# Mozard_2020-10-18.net
KiCad netlist of a schematic drawn in EAGLE
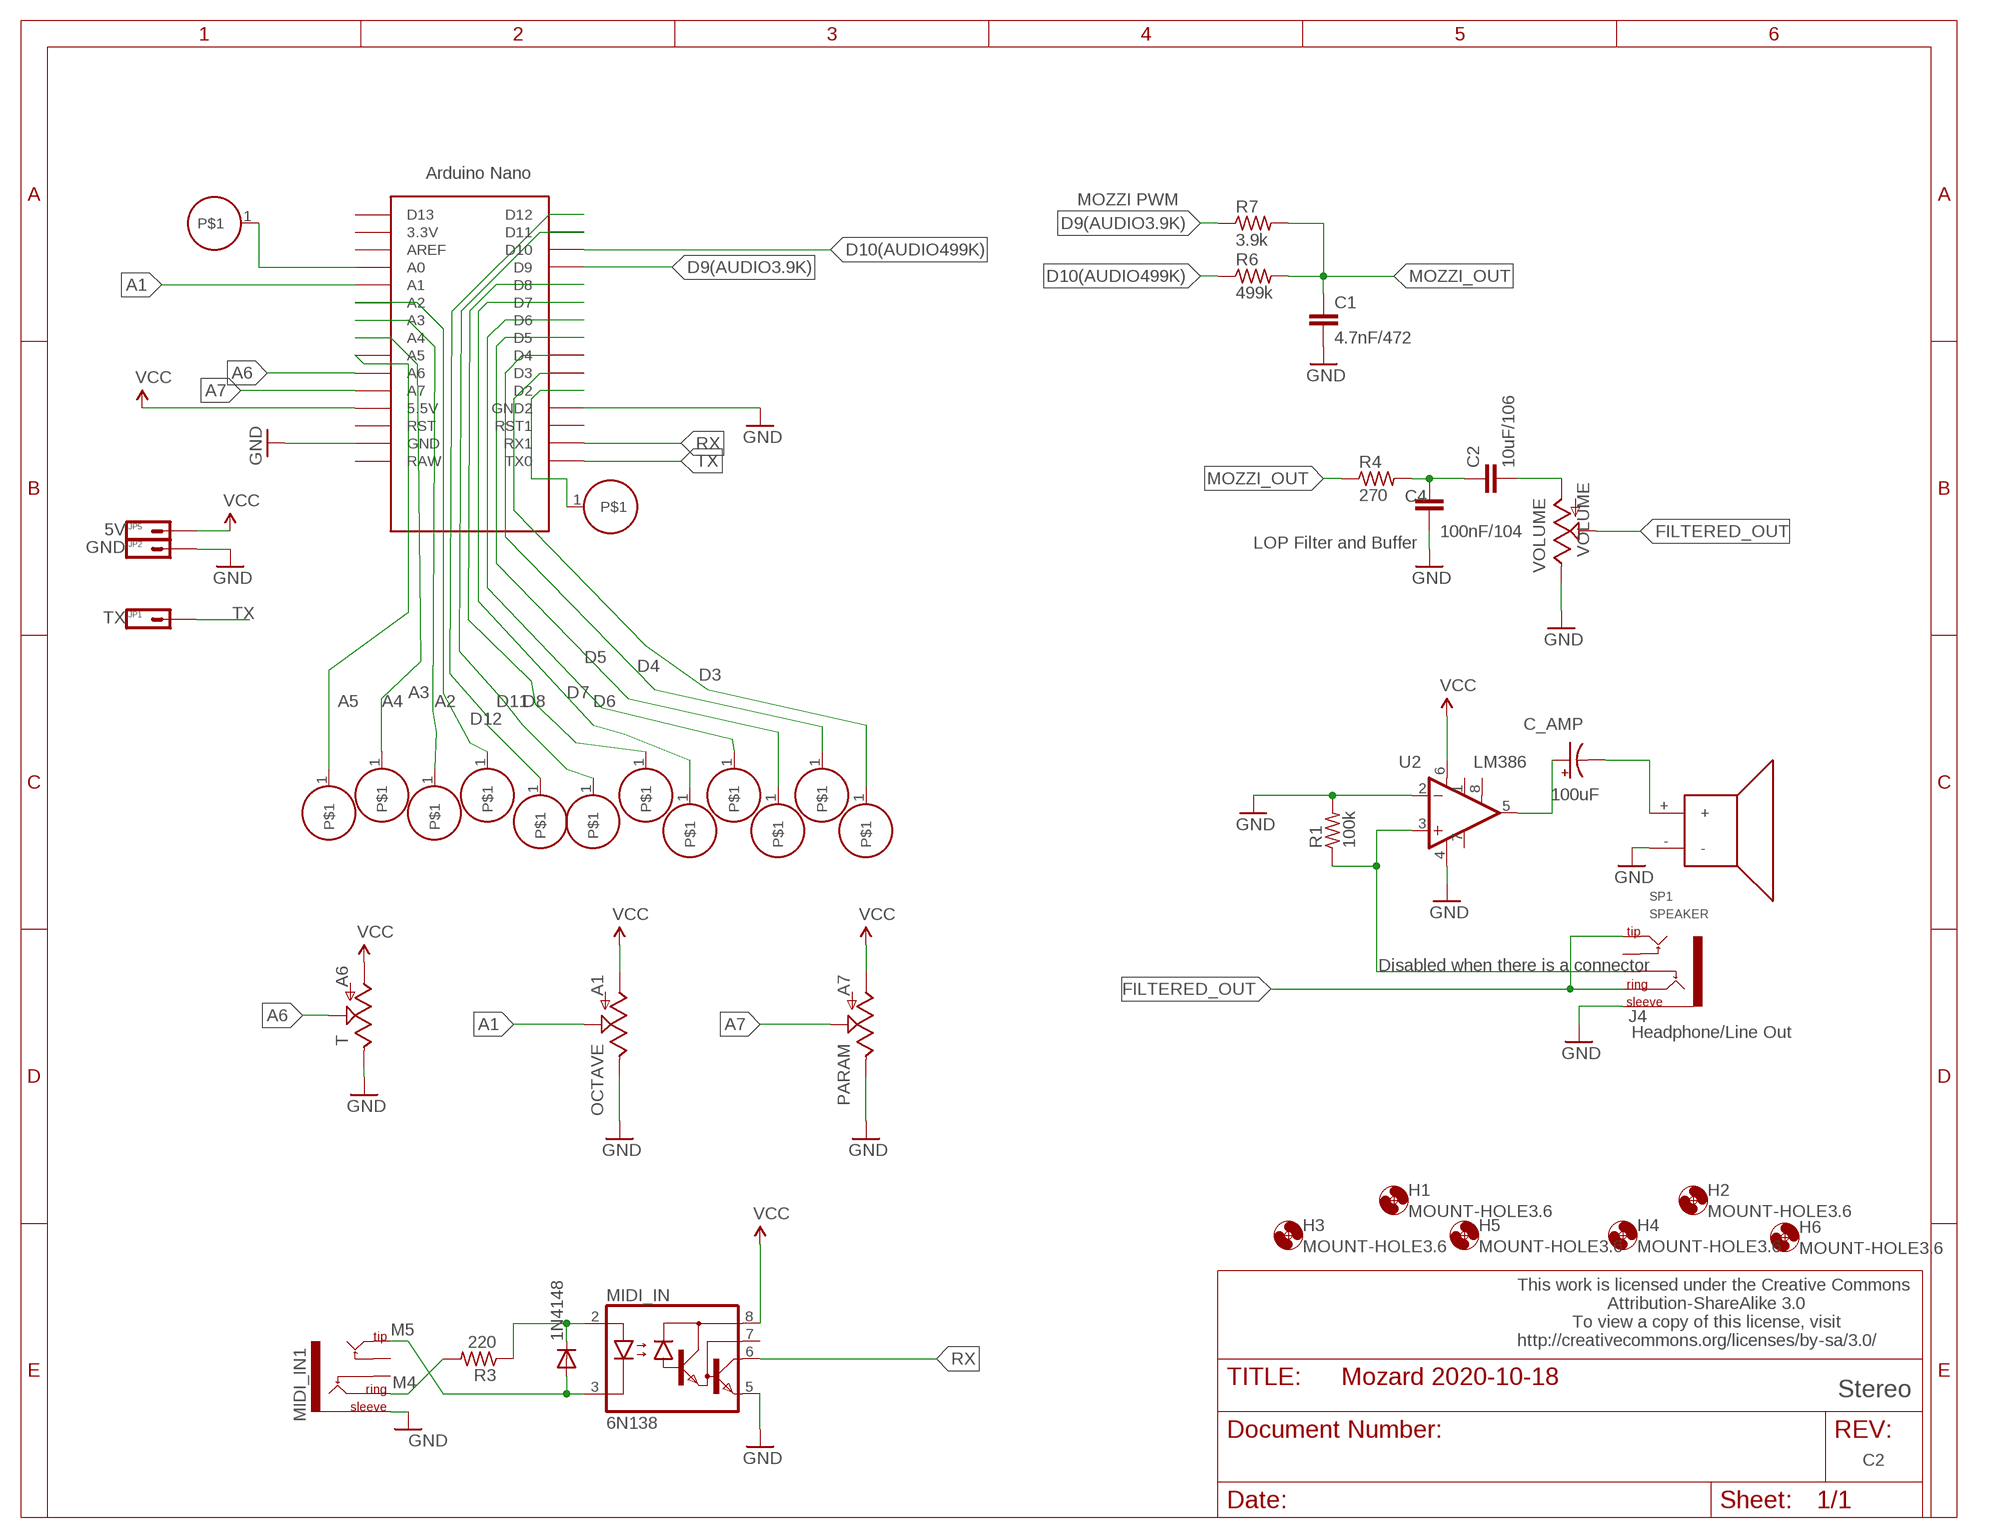
[diagram p0: schematic, sheet 1]

(export (version "E")
  (design (tool "Eeschema 10.0.6"))
  (components
    (comp (ref "1N4148")
      (value "1N4148")
      (footprint "eagle-import:DO41-10")
      (libsource (lib "eagle-import") (part "DIODE"))
    )
    (comp (ref "C1")
      (value "4.7nF/472")
      (footprint "eagle-import:CAP-PTH-SMALL-KIT")
      (libsource (lib "eagle-import") (part "0.1UF-50V-20%(PTH)KIT-EZ"))
    )
    (comp (ref "C2")
      (value "10uF/106")
      (footprint "eagle-import:CAP-PTH-SMALL-KIT")
      (libsource (lib "eagle-import") (part "0.1UF-50V-20%(PTH)KIT-EZ"))
    )
    (comp (ref "C4")
      (value "100nF/104")
      (footprint "eagle-import:CAP-PTH-SMALL-KIT")
      (libsource (lib "eagle-import") (part "0.1UF-50V-20%(PTH)KIT-EZ"))
    )
    (comp (ref "C_AMP")
      (value "100uF")
      (footprint "eagle-import:CPOL-RADIAL-10UF-25V")
      (libsource (lib "eagle-import") (part "CPOL-RADIAL-10UF-25V"))
    )
    (comp (ref "H1")
      (value "MOUNT-HOLE3.6")
      (footprint "eagle-import:3,6")
      (libsource (lib "eagle-import") (part "MOUNT-HOLE3.6"))
    )
    (comp (ref "H2")
      (value "MOUNT-HOLE3.6")
      (footprint "eagle-import:3,6")
      (libsource (lib "eagle-import") (part "MOUNT-HOLE3.6"))
    )
    (comp (ref "H3")
      (value "MOUNT-HOLE3.6")
      (footprint "eagle-import:3,6")
      (libsource (lib "eagle-import") (part "MOUNT-HOLE3.6"))
    )
    (comp (ref "H4")
      (value "MOUNT-HOLE3.6")
      (footprint "eagle-import:3,6")
      (libsource (lib "eagle-import") (part "MOUNT-HOLE3.6"))
    )
    (comp (ref "H5")
      (value "MOUNT-HOLE3.6")
      (footprint "eagle-import:3,6")
      (libsource (lib "eagle-import") (part "MOUNT-HOLE3.6"))
    )
    (comp (ref "H6")
      (value "MOUNT-HOLE3.6")
      (footprint "eagle-import:3,6")
      (libsource (lib "eagle-import") (part "MOUNT-HOLE3.6"))
    )
    (comp (ref "J4")
      (value "Headphone/Line Out")
      (footprint "eagle-import:AUDIO-JACK")
      (libsource (lib "eagle-import") (part "AUDIO-JACKPTH"))
    )
    (comp (ref "JP1")
      (value "TX")
      (footprint "eagle-import:1X01_SIDE_NAME")
      (libsource (lib "eagle-import") (part "HEADER-1X1"))
    )
    (comp (ref "JP2")
      (value "GND")
      (footprint "eagle-import:1X01_SIDE_NAME")
      (libsource (lib "eagle-import") (part "HEADER-1X1"))
    )
    (comp (ref "JP5")
      (value "5V")
      (footprint "eagle-import:1X01_SIDE_NAME")
      (libsource (lib "eagle-import") (part "HEADER-1X1"))
    )
    (comp (ref "MIDI_IN")
      (value "6N138")
      (footprint "eagle-import:DIL08")
      (fields (field (name "MF") "VISHAY/TELEFUNKEN"))
      (libsource (lib "eagle-import") (part "6N138"))
    )
    (comp (ref "MIDI_IN1")
      (value "AUDIO-JACKKIT")
      (footprint "eagle-import:AUDIO-JACK-KIT")
      (libsource (lib "eagle-import") (part "AUDIO-JACKKIT"))
    )
    (comp (ref "OCTAVE")
      (value "A1")
      (footprint "eagle-import:ALPS_POT")
      (libsource (lib "eagle-import") (part "POT"))
    )
    (comp (ref "PARAM")
      (value "A7")
      (footprint "eagle-import:ALPS_POT")
      (libsource (lib "eagle-import") (part "POT"))
    )
    (comp (ref "R1")
      (value "100k")
      (footprint "eagle-import:0204_7")
      (libsource (lib "eagle-import") (part "R-US_0204/7"))
    )
    (comp (ref "R3")
      (value "220")
      (footprint "eagle-import:0204_5")
      (libsource (lib "eagle-import") (part "R-US_0204/5"))
    )
    (comp (ref "R4")
      (value "270")
      (footprint "eagle-import:0204_7")
      (libsource (lib "eagle-import") (part "R-US_0204/7"))
    )
    (comp (ref "R6")
      (value "499k")
      (footprint "eagle-import:0204_7")
      (libsource (lib "eagle-import") (part "R-US_0204/7"))
    )
    (comp (ref "R7")
      (value "3.9k")
      (footprint "eagle-import:0204_7")
      (libsource (lib "eagle-import") (part "R-US_0204/7"))
    )
    (comp (ref "SP1")
      (value "SPEAKER")
      (footprint "eagle-import:PCB_MOUNT_SPEAKER")
      (fields (field (name "MFG") "SANCO"))
      (libsource (lib "eagle-import") (part "SPEAKERPCB_MOUNT"))
    )
    (comp (ref "T")
      (value "A6")
      (footprint "eagle-import:ALPS_POT")
      (libsource (lib "eagle-import") (part "POT"))
    )
    (comp (ref "U$1")
      (value "NANO")
      (footprint "eagle-import:NANO")
      (libsource (lib "eagle-import") (part "NANO"))
    )
    (comp (ref "U$2")
      (value "PCB-TOUCHPAD-1-PIN")
      (footprint "eagle-import:PCB-TOUCHPAD-1-PIN")
      (libsource (lib "eagle-import") (part "PCB-TOUCHPAD-1-PIN"))
    )
    (comp (ref "U$3")
      (value "PCB-TOUCHPAD-1-PIN")
      (footprint "eagle-import:PCB-TOUCHPAD-1-PIN")
      (libsource (lib "eagle-import") (part "PCB-TOUCHPAD-1-PIN"))
    )
    (comp (ref "U$4")
      (value "PCB-TOUCHPAD-1-PIN")
      (footprint "eagle-import:PCB-TOUCHPAD-1-PIN")
      (libsource (lib "eagle-import") (part "PCB-TOUCHPAD-1-PIN"))
    )
    (comp (ref "U$5")
      (value "PCB-TOUCHPAD-1-PIN")
      (footprint "eagle-import:PCB-TOUCHPAD-1-PIN")
      (libsource (lib "eagle-import") (part "PCB-TOUCHPAD-1-PIN"))
    )
    (comp (ref "U$6")
      (value "PCB-TOUCHPAD-1-PIN")
      (footprint "eagle-import:PCB-TOUCHPAD-1-PIN")
      (libsource (lib "eagle-import") (part "PCB-TOUCHPAD-1-PIN"))
    )
    (comp (ref "U$7")
      (value "PCB-TOUCHPAD-1-PIN")
      (footprint "eagle-import:PCB-TOUCHPAD-1-PIN")
      (libsource (lib "eagle-import") (part "PCB-TOUCHPAD-1-PIN"))
    )
    (comp (ref "U$8")
      (value "PCB-TOUCHPAD-1-PIN")
      (footprint "eagle-import:PCB-TOUCHPAD-1-PIN")
      (libsource (lib "eagle-import") (part "PCB-TOUCHPAD-1-PIN"))
    )
    (comp (ref "U$9")
      (value "PCB-TOUCHPAD-1-PIN")
      (footprint "eagle-import:PCB-TOUCHPAD-1-PIN")
      (libsource (lib "eagle-import") (part "PCB-TOUCHPAD-1-PIN"))
    )
    (comp (ref "U$10")
      (value "PCB-TOUCHPAD-1-PIN")
      (footprint "eagle-import:PCB-TOUCHPAD-1-PIN")
      (libsource (lib "eagle-import") (part "PCB-TOUCHPAD-1-PIN"))
    )
    (comp (ref "U$11")
      (value "PCB-TOUCHPAD-1-PIN")
      (footprint "eagle-import:PCB-TOUCHPAD-1-PIN")
      (libsource (lib "eagle-import") (part "PCB-TOUCHPAD-1-PIN"))
    )
    (comp (ref "U$12")
      (value "PCB-TOUCHPAD-1-PIN")
      (footprint "eagle-import:PCB-TOUCHPAD-1-PIN")
      (libsource (lib "eagle-import") (part "PCB-TOUCHPAD-1-PIN"))
    )
    (comp (ref "U$13")
      (value "PCB-TOUCHPAD-1-PIN")
      (footprint "eagle-import:PCB-TOUCHPAD-1-PIN")
      (libsource (lib "eagle-import") (part "PCB-TOUCHPAD-1-PIN"))
    )
    (comp (ref "U$14")
      (value "PCB-TOUCHPAD-1-PIN")
      (footprint "eagle-import:PCB-TOUCHPAD-1-PIN")
      (libsource (lib "eagle-import") (part "PCB-TOUCHPAD-1-PIN"))
    )
    (comp (ref "U$15")
      (value "PCB-TOUCHPAD-1-PIN")
      (footprint "eagle-import:PCB-TOUCHPAD-1-PIN")
      (libsource (lib "eagle-import") (part "PCB-TOUCHPAD-1-PIN"))
    )
    (comp (ref "U2")
      (value "LM386")
      (footprint "eagle-import:DIP08")
      (libsource (lib "eagle-import") (part "LM386"))
    )
    (comp (ref "VOLUME")
      (value "VOLUME")
      (footprint "eagle-import:ALPS_POT")
      (libsource (lib "eagle-import") (part "POT"))
    )
  )
  (nets
    (net (code "1") (name "/A2") (class "Default")
      (node (ref "U$1") (pin "A2") (pinfunction "A2_A2") (pintype "bidirectional"))
      (node (ref "U$5") (pin "1") (pinfunction "P$1_1") (pintype "bidirectional"))
    )
    (net (code "2") (name "/A3") (class "Default")
      (node (ref "U$1") (pin "A3") (pinfunction "A3_A3") (pintype "bidirectional"))
      (node (ref "U$4") (pin "1") (pinfunction "P$1_1") (pintype "bidirectional"))
    )
    (net (code "3") (name "/A4") (class "Default")
      (node (ref "U$1") (pin "A4") (pinfunction "A4_A4") (pintype "bidirectional"))
      (node (ref "U$3") (pin "1") (pinfunction "P$1_1") (pintype "bidirectional"))
    )
    (net (code "4") (name "/A5") (class "Default")
      (node (ref "U$1") (pin "A5") (pinfunction "A5_A5") (pintype "bidirectional"))
      (node (ref "U$2") (pin "1") (pinfunction "P$1_1") (pintype "bidirectional"))
    )
    (net (code "5") (name "/D3") (class "Default")
      (node (ref "U$1") (pin "D3") (pinfunction "D3_D3") (pintype "bidirectional"))
      (node (ref "U$13") (pin "1") (pinfunction "P$1_1") (pintype "bidirectional"))
    )
    (net (code "6") (name "/D4") (class "Default")
      (node (ref "U$1") (pin "D4") (pinfunction "D4_D4") (pintype "bidirectional"))
      (node (ref "U$12") (pin "1") (pinfunction "P$1_1") (pintype "bidirectional"))
    )
    (net (code "7") (name "/D5") (class "Default")
      (node (ref "U$1") (pin "D5") (pinfunction "D5_D5") (pintype "bidirectional"))
      (node (ref "U$11") (pin "1") (pinfunction "P$1_1") (pintype "bidirectional"))
    )
    (net (code "8") (name "/D6") (class "Default")
      (node (ref "U$1") (pin "D6") (pinfunction "D6_D6") (pintype "bidirectional"))
      (node (ref "U$10") (pin "1") (pinfunction "P$1_1") (pintype "bidirectional"))
    )
    (net (code "9") (name "/D7") (class "Default")
      (node (ref "U$1") (pin "D7") (pinfunction "D7_D7") (pintype "bidirectional"))
      (node (ref "U$9") (pin "1") (pinfunction "P$1_1") (pintype "bidirectional"))
    )
    (net (code "10") (name "/D8") (class "Default")
      (node (ref "U$1") (pin "D8") (pinfunction "D8_D8") (pintype "bidirectional"))
      (node (ref "U$8") (pin "1") (pinfunction "P$1_1") (pintype "bidirectional"))
    )
    (net (code "11") (name "/D11") (class "Default")
      (node (ref "U$1") (pin "D11") (pinfunction "D11_D11") (pintype "bidirectional"))
      (node (ref "U$7") (pin "1") (pinfunction "P$1_1") (pintype "bidirectional"))
    )
    (net (code "12") (name "/D12") (class "Default")
      (node (ref "U$1") (pin "D12") (pinfunction "D12_D12") (pintype "bidirectional"))
      (node (ref "U$6") (pin "1") (pinfunction "P$1_1") (pintype "bidirectional"))
    )
    (net (code "13") (name "/M4") (class "Default")
      (node (ref "MIDI_IN1") (pin "RING") (pinfunction "RING_RING") (pintype "bidirectional"))
      (node (ref "R3") (pin "2") (pinfunction "2_2") (pintype "passive"))
    )
    (net (code "14") (name "/M5") (class "Default")
      (node (ref "1N4148") (pin "A") (pinfunction "A_A") (pintype "passive"))
      (node (ref "MIDI_IN") (pin "3") (pinfunction "C_3") (pintype "passive"))
      (node (ref "MIDI_IN1") (pin "TIP") (pinfunction "TIP_TIP") (pintype "bidirectional"))
    )
    (net (code "15") (name "A1") (class "Default")
      (node (ref "OCTAVE") (pin "P$2") (pinfunction "S_P$2") (pintype "passive"))
      (node (ref "U$1") (pin "A1") (pinfunction "A1_A1") (pintype "bidirectional"))
    )
    (net (code "16") (name "A6") (class "Default")
      (node (ref "T") (pin "P$2") (pinfunction "S_P$2") (pintype "passive"))
      (node (ref "U$1") (pin "A6") (pinfunction "A6_A6") (pintype "bidirectional"))
    )
    (net (code "17") (name "A7") (class "Default")
      (node (ref "PARAM") (pin "P$2") (pinfunction "S_P$2") (pintype "passive"))
      (node (ref "U$1") (pin "A7") (pinfunction "A7_A7") (pintype "bidirectional"))
    )
    (net (code "18") (name "D9(AUDIO3.9K)") (class "Default")
      (node (ref "R7") (pin "1") (pinfunction "1_1") (pintype "passive"))
      (node (ref "U$1") (pin "D9") (pinfunction "D9_D9") (pintype "bidirectional"))
    )
    (net (code "19") (name "D10(AUDIO499K)") (class "Default")
      (node (ref "R6") (pin "1") (pinfunction "1_1") (pintype "passive"))
      (node (ref "U$1") (pin "D10") (pinfunction "D10_D10") (pintype "bidirectional"))
    )
    (net (code "20") (name "FILTERED_OUT") (class "Default")
      (node (ref "J4") (pin "RING") (pinfunction "RING_RING") (pintype "bidirectional"))
      (node (ref "J4") (pin "TIP") (pinfunction "TIP_TIP") (pintype "bidirectional"))
      (node (ref "VOLUME") (pin "P$2") (pinfunction "S_P$2") (pintype "passive"))
    )
    (net (code "21") (name "GND") (class "Default")
      (node (ref "C1") (pin "2") (pinfunction "2_2") (pintype "passive"))
      (node (ref "C4") (pin "2") (pinfunction "2_2") (pintype "passive"))
      (node (ref "J4") (pin "SLEEVE") (pinfunction "SLEEVE_SLEEVE") (pintype "bidirectional"))
      (node (ref "JP2") (pin "1") (pinfunction "1_1") (pintype "passive"))
      (node (ref "MIDI_IN") (pin "5") (pinfunction "GND_5") (pintype "passive"))
      (node (ref "MIDI_IN1") (pin "SLEEVE") (pinfunction "SLEEVE_SLEEVE") (pintype "bidirectional"))
      (node (ref "OCTAVE") (pin "P$1") (pinfunction "E_P$1") (pintype "passive"))
      (node (ref "PARAM") (pin "P$1") (pinfunction "E_P$1") (pintype "passive"))
      (node (ref "R1") (pin "2") (pinfunction "2_2") (pintype "passive"))
      (node (ref "SP1") (pin "-") (pinfunction "-_-") (pintype "bidirectional"))
      (node (ref "T") (pin "P$1") (pinfunction "E_P$1") (pintype "passive"))
      (node (ref "U$1") (pin "GND") (pinfunction "GND_GND") (pintype "bidirectional"))
      (node (ref "U$1") (pin "GND1") (pinfunction "GND2_GND1") (pintype "bidirectional"))
      (node (ref "U2") (pin "2") (pinfunction "-IN_2") (pintype "input"))
      (node (ref "U2") (pin "4") (pinfunction "V-_4") (pintype "power_in"))
      (node (ref "VOLUME") (pin "P$1") (pinfunction "E_P$1") (pintype "passive"))
    )
    (net (code "22") (name "MOZZI_OUT") (class "Default")
      (node (ref "C1") (pin "1") (pinfunction "1_1") (pintype "passive"))
      (node (ref "R4") (pin "1") (pinfunction "1_1") (pintype "passive"))
      (node (ref "R6") (pin "2") (pinfunction "2_2") (pintype "passive"))
      (node (ref "R7") (pin "2") (pinfunction "2_2") (pintype "passive"))
    )
    (net (code "23") (name "Net-(C2-Pad1)") (class "Default")
      (node (ref "C2") (pin "1") (pinfunction "1_1") (pintype "passive"))
      (node (ref "C4") (pin "1") (pinfunction "1_1") (pintype "passive"))
      (node (ref "R4") (pin "2") (pinfunction "2_2") (pintype "passive"))
    )
    (net (code "24") (name "Net-(C_AMP-Pad-)") (class "Default")
      (node (ref "C_AMP") (pin "-") (pinfunction "-_-") (pintype "passive"))
      (node (ref "SP1") (pin "+") (pinfunction "+_+") (pintype "bidirectional"))
    )
    (net (code "25") (name "Net-(MIDI_IN-A)") (class "Default")
      (node (ref "1N4148") (pin "C") (pinfunction "C_C") (pintype "passive"))
      (node (ref "MIDI_IN") (pin "2") (pinfunction "A_2") (pintype "passive"))
      (node (ref "R3") (pin "1") (pinfunction "1_1") (pintype "passive"))
    )
    (net (code "26") (name "Net-(U$14-P$1)") (class "Default")
      (node (ref "U$1") (pin "D2") (pinfunction "D2_D2") (pintype "bidirectional"))
      (node (ref "U$14") (pin "1") (pinfunction "P$1_1") (pintype "bidirectional"))
    )
    (net (code "27") (name "Net-(U$15-P$1)") (class "Default")
      (node (ref "U$1") (pin "A0") (pinfunction "A0_A0") (pintype "bidirectional"))
      (node (ref "U$15") (pin "1") (pinfunction "P$1_1") (pintype "bidirectional"))
    )
    (net (code "28") (name "Net-(U2-+IN)") (class "Default")
      (node (ref "J4") (pin "RSH") (pinfunction "RSH_RSH") (pintype "bidirectional"))
      (node (ref "R1") (pin "1") (pinfunction "1_1") (pintype "passive"))
      (node (ref "U2") (pin "3") (pinfunction "+IN_3") (pintype "input"))
    )
    (net (code "29") (name "Net-(U2-OUT)") (class "Default")
      (node (ref "C_AMP") (pin "+") (pinfunction "+_+") (pintype "passive"))
      (node (ref "U2") (pin "5") (pinfunction "OUT_5") (pintype "output"))
    )
    (net (code "30") (name "Net-(VOLUME-A)") (class "Default")
      (node (ref "C2") (pin "2") (pinfunction "2_2") (pintype "passive"))
      (node (ref "VOLUME") (pin "P$3") (pinfunction "A_P$3") (pintype "passive"))
    )
    (net (code "31") (name "RX") (class "Default")
      (node (ref "MIDI_IN") (pin "6") (pinfunction "VO_6") (pintype "passive"))
      (node (ref "U$1") (pin "RX1") (pinfunction "RX1_RX1") (pintype "bidirectional"))
    )
    (net (code "32") (name "TX") (class "Default")
      (node (ref "JP1") (pin "1") (pinfunction "1_1") (pintype "passive"))
      (node (ref "U$1") (pin "TX0") (pinfunction "TX0_TX0") (pintype "bidirectional"))
    )
    (net (code "33") (name "VCC") (class "Default")
      (node (ref "JP5") (pin "1") (pinfunction "1_1") (pintype "passive"))
      (node (ref "MIDI_IN") (pin "8") (pinfunction "VCC_8") (pintype "passive"))
      (node (ref "OCTAVE") (pin "P$3") (pinfunction "A_P$3") (pintype "passive"))
      (node (ref "PARAM") (pin "P$3") (pinfunction "A_P$3") (pintype "passive"))
      (node (ref "T") (pin "P$3") (pinfunction "A_P$3") (pintype "passive"))
      (node (ref "U$1") (pin "5V") (pinfunction "5.5V_5V") (pintype "bidirectional"))
      (node (ref "U2") (pin "6") (pinfunction "V+_6") (pintype "power_in"))
    )
    (net (code "34") (name "unconnected-(J4-PadTSH)") (class "Default")
      (node (ref "J4") (pin "TSH") (pinfunction "TSH_TSH") (pintype "bidirectional"))
    )
    (net (code "35") (name "unconnected-(MIDI_IN-VB-Pad7)") (class "Default")
      (node (ref "MIDI_IN") (pin "7") (pinfunction "VB_7") (pintype "passive"))
    )
    (net (code "36") (name "unconnected-(MIDI_IN1-PadRSH)") (class "Default")
      (node (ref "MIDI_IN1") (pin "RSH") (pinfunction "RSH_RSH") (pintype "bidirectional"))
    )
    (net (code "37") (name "unconnected-(MIDI_IN1-PadTSH)") (class "Default")
      (node (ref "MIDI_IN1") (pin "TSH") (pinfunction "TSH_TSH") (pintype "bidirectional"))
    )
    (net (code "38") (name "unconnected-(U$1-Pad3.3V)") (class "Default")
      (node (ref "U$1") (pin "3.3V") (pinfunction "3.3V_3.3V") (pintype "bidirectional"))
    )
    (net (code "39") (name "unconnected-(U$1-PadAREF)") (class "Default")
      (node (ref "U$1") (pin "AREF") (pinfunction "AREF_AREF") (pintype "bidirectional"))
    )
    (net (code "40") (name "unconnected-(U$1-PadD13)") (class "Default")
      (node (ref "U$1") (pin "D13") (pinfunction "D13_D13") (pintype "bidirectional"))
    )
    (net (code "41") (name "unconnected-(U$1-PadRAW)") (class "Default")
      (node (ref "U$1") (pin "RAW") (pinfunction "RAW_RAW") (pintype "bidirectional"))
    )
    (net (code "42") (name "unconnected-(U$1-PadRST)") (class "Default")
      (node (ref "U$1") (pin "RST") (pinfunction "RST_RST") (pintype "bidirectional"))
    )
    (net (code "43") (name "unconnected-(U$1-PadRST1)") (class "Default")
      (node (ref "U$1") (pin "RST1") (pinfunction "RST1_RST1") (pintype "bidirectional"))
    )
    (net (code "44") (name "unconnected-(U2-BP-Pad7)") (class "Default")
      (node (ref "U2") (pin "7") (pinfunction "BP_7") (pintype "bidirectional"))
    )
    (net (code "45") (name "unconnected-(U2-GAIN-Pad1)") (class "Default")
      (node (ref "U2") (pin "1") (pinfunction "GAIN_1") (pintype "bidirectional"))
    )
    (net (code "46") (name "unconnected-(U2-GAIN-Pad8)") (class "Default")
      (node (ref "U2") (pin "8") (pinfunction "GAIN_8") (pintype "bidirectional"))
    )
  )
)
